# Sheet1.net
KiCad netlist of a schematic drawn in Altium Designer
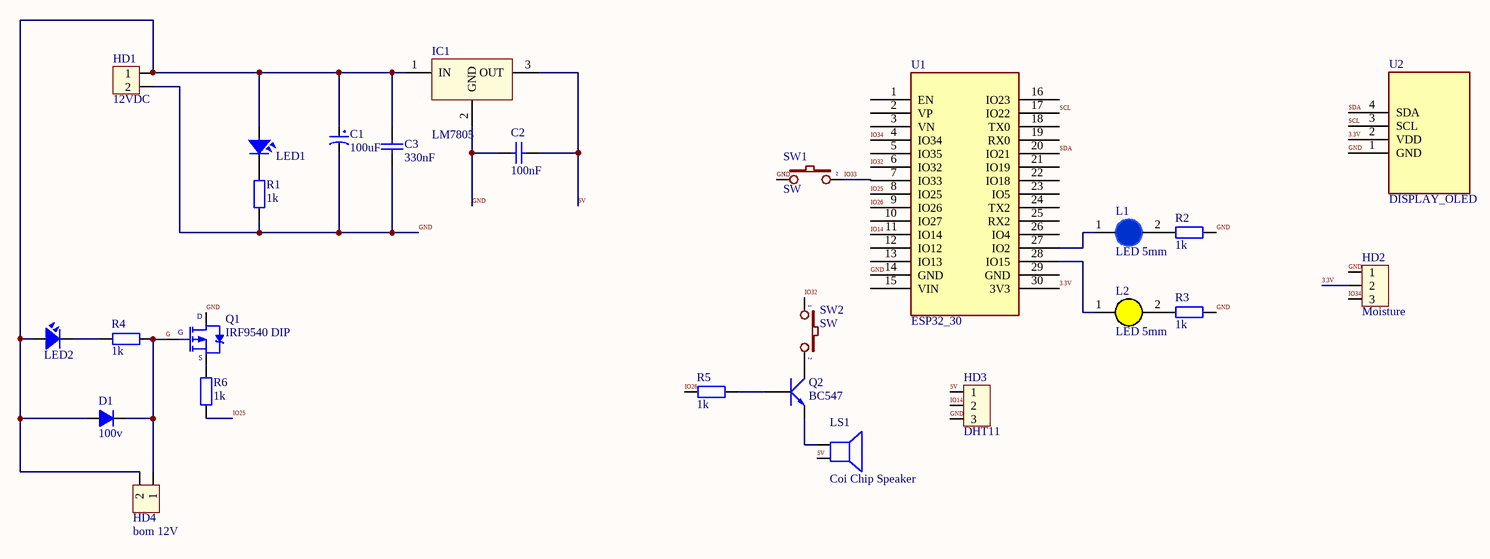
[diagram p0: Sheet1.SchDoc]

(export (version "E")
  (design (tool "Eeschema 10.0.6"))
  (components
    (comp (ref "C1")
      (value "100uF")
      (footprint "tu hoa 6.5mm")
      (description "Cắm")
      (libsource (lib "Tu dien") (part "Tu Hoa 100uF 35V 6x8"))
    )
    (comp (ref "C2")
      (value "100nF")
      (footprint "tu tantalum dip5.08")
      (description "Cắm")
      (libsource (lib "Tu dien") (part "Tu tantalum 100nF 50V 20% DIP5.08"))
    )
    (comp (ref "C3")
      (value "330nF")
      (footprint "Tu tantalum dip5.08")
      (description "Cắm")
      (libsource (lib "Tu dien") (part "Tu tantalum 330nF 50V 20% DIP5.08"))
    )
    (comp (ref "D1")
      (value "100v")
      (footprint "DIODE 1A")
      (description "Cắm")
      (libsource (lib "Diode") (part "Diode 1N4007"))
    )
    (comp (ref "HD1")
      (value "12VDC")
      (footprint "HED2")
      (description "Header 2 (Green)")
      (libsource (lib "syhaunguyen") (part "Hed2"))
    )
    (comp (ref "HD2")
      (value "Moisture")
      (footprint "HED3")
      (description "Header 3 (Green)")
      (libsource (lib "syhaunguyen") (part "Hed3"))
    )
    (comp (ref "HD3")
      (value "DHT11")
      (footprint "HED3")
      (description "Header 3 (Green)")
      (libsource (lib "syhaunguyen") (part "Hed3"))
    )
    (comp (ref "HD4")
      (value "bom 12V")
      (footprint "HED2")
      (description "Header 2 (Green)")
      (libsource (lib "syhaunguyen") (part "Hed2"))
    )
    (comp (ref "IC1")
      (value "LM7805")
      (footprint "QTO-220")
      (description "On ap +, from + 5 to + 24VDC")
      (libsource (lib "syhaunguyen") (part "LM78xx"))
    )
    (comp (ref "L1")
      (value "LED 5mm")
      (footprint "LED-5MM-BLUE")
      (description "Cắm")
      (libsource (lib "Led") (part "LED 5mm Xanh Duong"))
    )
    (comp (ref "L2")
      (value "LED 5mm")
      (footprint "LED-5MM-Yellow")
      (description "Cắm")
      (libsource (lib "Led") (part "LED 5mm Vang"))
    )
    (comp (ref "LED1")
      (value "LED")
      (footprint "LED-3")
      (description "LED Single colour Green and Red")
      (libsource (lib "syhaunguyen") (part "LED"))
    )
    (comp (ref "LED2")
      (value "LED")
      (footprint "LED-3")
      (description "LED Single colour Green and Red")
      (libsource (lib "syhaunguyen") (part "LED"))
    )
    (comp (ref "LS1")
      (value "Coi Chip Speaker")
      (footprint "Coi Chip Speacker")
      (description "Còi chip")
      (libsource (lib "Component") (part "Coi Chip Speaker"))
    )
    (comp (ref "Q1")
      (value "IRF9540 DIP")
      (footprint "TO220")
      (description "P-Channel Power MOSFET")
      (fields (field (name "PUBLISHER") "Altium Limited"))
      (libsource (lib "TranFet") (part "IRF9540 DIP"))
    )
    (comp (ref "Q2")
      (value "BC547")
      (footprint "TO92")
      (description "NPN transistor")
      (libsource (lib "TranFet") (part "C1815"))
    )
    (comp (ref "R1")
      (value "1k")
      (footprint "tro vach 1w")
      (description "Cắm")
      (libsource (lib "Dien Tro") (part "Tro Vach 1W 5% 1k"))
    )
    (comp (ref "R2")
      (value "1k")
      (footprint "tro vach 1w")
      (description "Cắm")
      (libsource (lib "Dien Tro") (part "Tro Vach 1W 5% 1k"))
    )
    (comp (ref "R3")
      (value "1k")
      (footprint "tro vach 1w")
      (description "Cắm")
      (libsource (lib "Dien Tro") (part "Tro Vach 1W 5% 1k"))
    )
    (comp (ref "R4")
      (value "1k")
      (footprint "tro vach 1w")
      (description "Cắm")
      (libsource (lib "Dien Tro") (part "Tro Vach 1W 5% 1k"))
    )
    (comp (ref "R5")
      (value "1k")
      (footprint "tro vach 1w")
      (description "Cắm")
      (libsource (lib "Dien Tro") (part "Tro Vach 1W 5% 1k"))
    )
    (comp (ref "R6")
      (value "1k")
      (footprint "tro vach 1w")
      (description "Cắm")
      (libsource (lib "Dien Tro") (part "Tro Vach 1W 5% 1k"))
    )
    (comp (ref "SW1")
      (value "SW")
      (footprint "SW2")
      (description "Switch button 2 pin")
      (libsource (lib "syhaunguyen") (part "SW2"))
    )
    (comp (ref "SW2")
      (value "SW")
      (footprint "SW2")
      (description "Switch button 2 pin")
      (libsource (lib "syhaunguyen") (part "SW2"))
    )
    (comp (ref "U1")
      (value "ESP32_30")
      (footprint "ESP32_30")
      (description "Microcontoller Board 30 Pins Wifi 2.4GHz BLE 4.2 ESP32-WROOM-32D")
      (libsource (lib "Espressif Microcontrollers") (part "ESP32_30"))
    )
    (comp (ref "U2")
      (value "DISPLAY_OLED")
      (footprint "DISPLAY_OLED")
      (description "Display Oled 128x64 0.96\" I2C.")
      (libsource (lib "Displays") (part "DISPLAY_OLED"))
    )
  )
  (nets
    (net (code "1") (name "/3.3V") (class "Default")
      (node (ref "HD2") (pin "2") (pinfunction "2_2") (pintype "passive"))
      (node (ref "U1") (pin "30") (pinfunction "3V3_30") (pintype "passive"))
      (node (ref "U2") (pin "2") (pinfunction "VDD_2") (pintype "tri_state"))
    )
    (net (code "2") (name "/5V") (class "Default")
      (node (ref "C2") (pin "1") (pinfunction "1_1") (pintype "passive"))
      (node (ref "HD3") (pin "1") (pinfunction "1_1") (pintype "passive"))
      (node (ref "IC1") (pin "3") (pinfunction "OUT_3") (pintype "passive"))
      (node (ref "LS1") (pin "2") (pinfunction "2_2") (pintype "passive"))
    )
    (net (code "3") (name "/G") (class "Default")
      (node (ref "D1") (pin "2") (pinfunction "K_2") (pintype "passive"))
      (node (ref "HD4") (pin "1") (pinfunction "1_1") (pintype "passive"))
      (node (ref "Q1") (pin "1") (pinfunction "G_1") (pintype "passive"))
      (node (ref "R4") (pin "1") (pinfunction "1_1") (pintype "passive"))
    )
    (net (code "4") (name "/GND") (class "Default")
      (node (ref "C1") (pin "2") (pinfunction "2_2") (pintype "passive"))
      (node (ref "C2") (pin "2") (pinfunction "2_2") (pintype "passive"))
      (node (ref "C3") (pin "2") (pinfunction "2_2") (pintype "passive"))
      (node (ref "HD1") (pin "2") (pinfunction "2_2") (pintype "passive"))
      (node (ref "HD2") (pin "1") (pinfunction "1_1") (pintype "passive"))
      (node (ref "HD3") (pin "3") (pinfunction "3_3") (pintype "passive"))
      (node (ref "IC1") (pin "2") (pinfunction "GND_2") (pintype "passive"))
      (node (ref "Q1") (pin "2") (pinfunction "D_2") (pintype "passive"))
      (node (ref "R1") (pin "1") (pinfunction "1_1") (pintype "passive"))
      (node (ref "R2") (pin "2") (pinfunction "2_2") (pintype "passive"))
      (node (ref "R3") (pin "2") (pinfunction "2_2") (pintype "passive"))
      (node (ref "SW1") (pin "1") (pinfunction "1_1") (pintype "passive"))
      (node (ref "U1") (pin "14") (pinfunction "GND_14") (pintype "passive"))
      (node (ref "U2") (pin "1") (pinfunction "GND_1") (pintype "tri_state"))
    )
    (net (code "5") (name "/IO14") (class "Default")
      (node (ref "HD3") (pin "2") (pinfunction "2_2") (pintype "passive"))
      (node (ref "U1") (pin "11") (pinfunction "IO14_11") (pintype "passive"))
    )
    (net (code "6") (name "/IO25") (class "Default")
      (node (ref "R6") (pin "1") (pinfunction "1_1") (pintype "passive"))
      (node (ref "U1") (pin "8") (pinfunction "IO25_8") (pintype "passive"))
    )
    (net (code "7") (name "/IO26") (class "Default")
      (node (ref "R5") (pin "1") (pinfunction "1_1") (pintype "passive"))
      (node (ref "U1") (pin "9") (pinfunction "IO26_9") (pintype "passive"))
    )
    (net (code "8") (name "/IO32") (class "Default")
      (node (ref "SW2") (pin "1") (pinfunction "1_1") (pintype "passive"))
      (node (ref "U1") (pin "6") (pinfunction "IO32_6") (pintype "passive"))
    )
    (net (code "9") (name "/IO33") (class "Default")
      (node (ref "SW1") (pin "2") (pinfunction "2_2") (pintype "passive"))
      (node (ref "U1") (pin "7") (pinfunction "IO33_7") (pintype "passive"))
    )
    (net (code "10") (name "/IO34") (class "Default")
      (node (ref "HD2") (pin "3") (pinfunction "3_3") (pintype "passive"))
      (node (ref "U1") (pin "4") (pinfunction "IO34_4") (pintype "passive"))
    )
    (net (code "11") (name "/SCL") (class "Default")
      (node (ref "U1") (pin "17") (pinfunction "IO22_17") (pintype "passive"))
      (node (ref "U2") (pin "3") (pinfunction "SCL_3") (pintype "tri_state"))
    )
    (net (code "12") (name "/SDA") (class "Default")
      (node (ref "U1") (pin "20") (pinfunction "IO21_20") (pintype "passive"))
      (node (ref "U2") (pin "4") (pinfunction "SDA_4") (pintype "tri_state"))
    )
    (net (code "13") (name "Net-(D1-A)") (class "Default")
      (node (ref "C1") (pin "1") (pinfunction "1_1") (pintype "passive"))
      (node (ref "C3") (pin "1") (pinfunction "1_1") (pintype "passive"))
      (node (ref "D1") (pin "1") (pinfunction "A_1") (pintype "passive"))
      (node (ref "HD1") (pin "1") (pinfunction "1_1") (pintype "passive"))
      (node (ref "HD4") (pin "2") (pinfunction "2_2") (pintype "passive"))
      (node (ref "IC1") (pin "1") (pinfunction "IN_1") (pintype "passive"))
      (node (ref "LED1") (pin "1") (pinfunction "1_1") (pintype "passive"))
      (node (ref "LED2") (pin "1") (pinfunction "1_1") (pintype "passive"))
    )
    (net (code "14") (name "Net-(L1-A)") (class "Default")
      (node (ref "L1") (pin "1") (pinfunction "A_1") (pintype "passive"))
      (node (ref "U1") (pin "27") (pinfunction "IO2_27") (pintype "passive"))
    )
    (net (code "15") (name "Net-(L1-K)") (class "Default")
      (node (ref "L1") (pin "2") (pinfunction "K_2") (pintype "passive"))
      (node (ref "R2") (pin "1") (pinfunction "1_1") (pintype "passive"))
    )
    (net (code "16") (name "Net-(L2-A)") (class "Default")
      (node (ref "L2") (pin "1") (pinfunction "A_1") (pintype "passive"))
      (node (ref "U1") (pin "28") (pinfunction "IO15_28") (pintype "passive"))
    )
    (net (code "17") (name "Net-(L2-K)") (class "Default")
      (node (ref "L2") (pin "2") (pinfunction "K_2") (pintype "passive"))
      (node (ref "R3") (pin "1") (pinfunction "1_1") (pintype "passive"))
    )
    (net (code "18") (name "Net-(LED1-Pad2)") (class "Default")
      (node (ref "LED1") (pin "2") (pinfunction "2_2") (pintype "passive"))
      (node (ref "R1") (pin "2") (pinfunction "2_2") (pintype "passive"))
    )
    (net (code "19") (name "Net-(LED2-Pad2)") (class "Default")
      (node (ref "LED2") (pin "2") (pinfunction "2_2") (pintype "passive"))
      (node (ref "R4") (pin "2") (pinfunction "2_2") (pintype "passive"))
    )
    (net (code "20") (name "Net-(Q1-S)") (class "Default")
      (node (ref "Q1") (pin "3") (pinfunction "S_3") (pintype "passive"))
      (node (ref "R6") (pin "2") (pinfunction "2_2") (pintype "passive"))
    )
    (net (code "21") (name "Net-(Q2-B)") (class "Default")
      (node (ref "Q2") (pin "3") (pinfunction "B_3") (pintype "passive"))
      (node (ref "R5") (pin "2") (pinfunction "2_2") (pintype "passive"))
    )
    (net (code "22") (name "Net-(Q2-C)") (class "Default")
      (node (ref "Q2") (pin "2") (pinfunction "C_2") (pintype "passive"))
      (node (ref "SW2") (pin "2") (pinfunction "2_2") (pintype "passive"))
    )
    (net (code "23") (name "Net-(Q2-E)") (class "Default")
      (node (ref "LS1") (pin "1") (pinfunction "1_1") (pintype "passive"))
      (node (ref "Q2") (pin "1") (pinfunction "E_1") (pintype "passive"))
    )
    (net (code "24") (name "unconnected-(U1-EN-Pad1)") (class "Default")
      (node (ref "U1") (pin "1") (pinfunction "EN_1") (pintype "passive"))
    )
    (net (code "25") (name "unconnected-(U1-GND-Pad29)") (class "Default")
      (node (ref "U1") (pin "29") (pinfunction "GND_29") (pintype "passive"))
    )
    (net (code "26") (name "unconnected-(U1-IO4-Pad26)") (class "Default")
      (node (ref "U1") (pin "26") (pinfunction "IO4_26") (pintype "passive"))
    )
    (net (code "27") (name "unconnected-(U1-IO5-Pad23)") (class "Default")
      (node (ref "U1") (pin "23") (pinfunction "IO5_23") (pintype "passive"))
    )
    (net (code "28") (name "unconnected-(U1-IO12-Pad12)") (class "Default")
      (node (ref "U1") (pin "12") (pinfunction "IO12_12") (pintype "passive"))
    )
    (net (code "29") (name "unconnected-(U1-IO13-Pad13)") (class "Default")
      (node (ref "U1") (pin "13") (pinfunction "IO13_13") (pintype "passive"))
    )
    (net (code "30") (name "unconnected-(U1-IO18-Pad22)") (class "Default")
      (node (ref "U1") (pin "22") (pinfunction "IO18_22") (pintype "passive"))
    )
    (net (code "31") (name "unconnected-(U1-IO19-Pad21)") (class "Default")
      (node (ref "U1") (pin "21") (pinfunction "IO19_21") (pintype "passive"))
    )
    (net (code "32") (name "unconnected-(U1-IO23-Pad16)") (class "Default")
      (node (ref "U1") (pin "16") (pinfunction "IO23_16") (pintype "passive"))
    )
    (net (code "33") (name "unconnected-(U1-IO27-Pad10)") (class "Default")
      (node (ref "U1") (pin "10") (pinfunction "IO27_10") (pintype "passive"))
    )
    (net (code "34") (name "unconnected-(U1-IO35-Pad5)") (class "Default")
      (node (ref "U1") (pin "5") (pinfunction "IO35_5") (pintype "passive"))
    )
    (net (code "35") (name "unconnected-(U1-RX0-Pad19)") (class "Default")
      (node (ref "U1") (pin "19") (pinfunction "RX0_19") (pintype "passive"))
    )
    (net (code "36") (name "unconnected-(U1-RX2-Pad25)") (class "Default")
      (node (ref "U1") (pin "25") (pinfunction "RX2_25") (pintype "passive"))
    )
    (net (code "37") (name "unconnected-(U1-TX0-Pad18)") (class "Default")
      (node (ref "U1") (pin "18") (pinfunction "TX0_18") (pintype "passive"))
    )
    (net (code "38") (name "unconnected-(U1-TX2-Pad24)") (class "Default")
      (node (ref "U1") (pin "24") (pinfunction "TX2_24") (pintype "passive"))
    )
    (net (code "39") (name "unconnected-(U1-VIN-Pad15)") (class "Default")
      (node (ref "U1") (pin "15") (pinfunction "VIN_15") (pintype "passive"))
    )
    (net (code "40") (name "unconnected-(U1-VN-Pad3)") (class "Default")
      (node (ref "U1") (pin "3") (pinfunction "VN_3") (pintype "passive"))
    )
    (net (code "41") (name "unconnected-(U1-VP-Pad2)") (class "Default")
      (node (ref "U1") (pin "2") (pinfunction "VP_2") (pintype "passive"))
    )
  )
)
